# PhotoBoothRaspPi.net
KiCad netlist of a schematic drawn in EAGLE
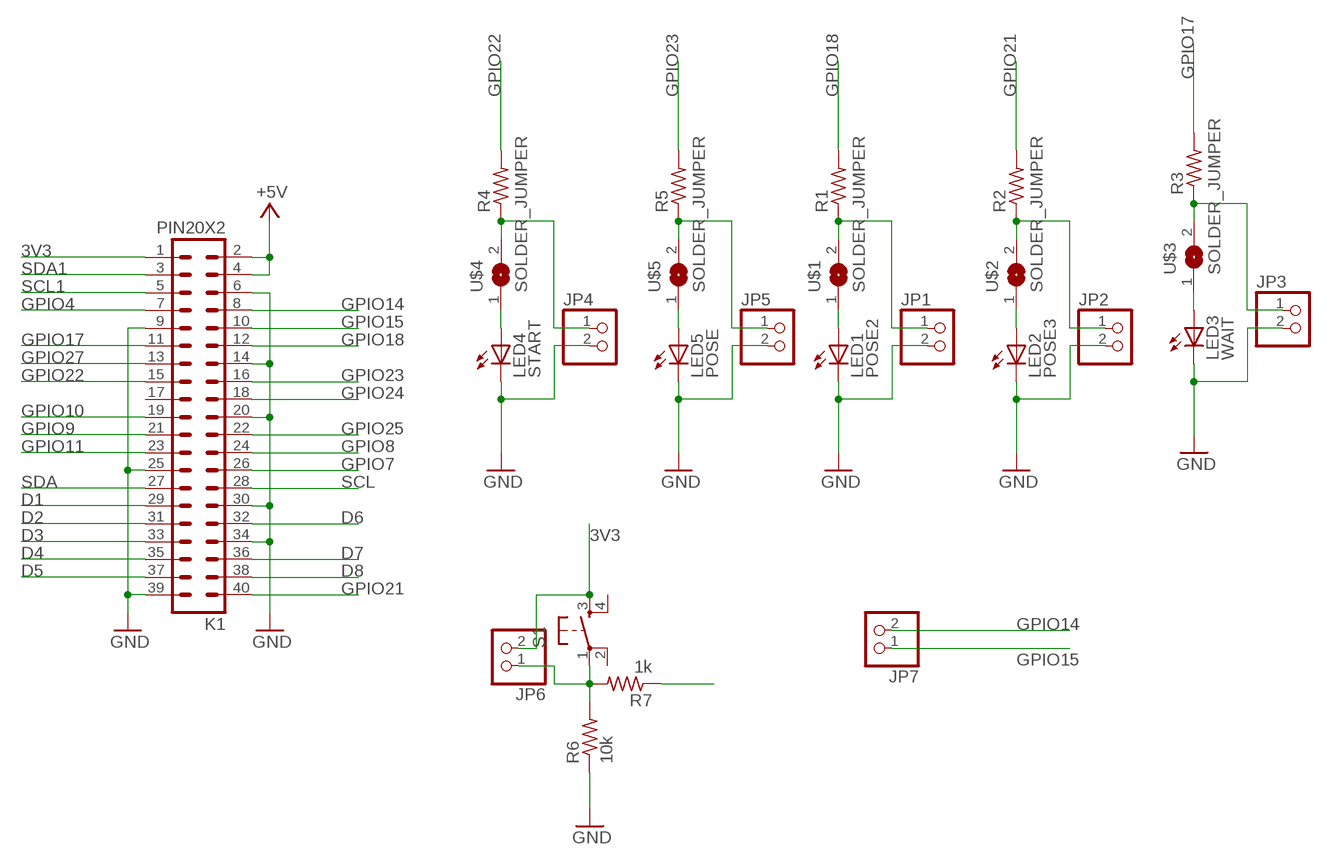
[diagram p0: schematic, sheet 1]

(export (version "E")
  (design (tool "Eeschema 10.0.6"))
  (components
    (comp (ref "JP1")
      (value "PINHD-1X2")
      (footprint "eagle-import:1X02")
      (libsource (lib "eagle-import") (part "PINHD-1X2"))
    )
    (comp (ref "JP2")
      (value "PINHD-1X2")
      (footprint "eagle-import:1X02")
      (libsource (lib "eagle-import") (part "PINHD-1X2"))
    )
    (comp (ref "JP3")
      (value "PINHD-1X2")
      (footprint "eagle-import:1X02")
      (libsource (lib "eagle-import") (part "PINHD-1X2"))
    )
    (comp (ref "JP4")
      (value "PINHD-1X2")
      (footprint "eagle-import:1X02")
      (libsource (lib "eagle-import") (part "PINHD-1X2"))
    )
    (comp (ref "JP5")
      (value "PINHD-1X2")
      (footprint "eagle-import:1X02")
      (libsource (lib "eagle-import") (part "PINHD-1X2"))
    )
    (comp (ref "JP6")
      (value "PINHD-1X2")
      (footprint "eagle-import:1X02")
      (libsource (lib "eagle-import") (part "PINHD-1X2"))
    )
    (comp (ref "JP7")
      (value "PINHD-1X2")
      (footprint "eagle-import:1X02")
      (libsource (lib "eagle-import") (part "PINHD-1X2"))
    )
    (comp (ref "K1")
      (value "PIN20X2")
      (footprint "eagle-import:PIN_20X2")
      (libsource (lib "eagle-import") (part "PIN20X2"))
    )
    (comp (ref "LED1")
      (value "POSE2")
      (footprint "eagle-import:CHIPLED_1206")
      (libsource (lib "eagle-import") (part "LEDCHIPLED_1206"))
    )
    (comp (ref "LED2")
      (value "POSE3")
      (footprint "eagle-import:CHIPLED_1206")
      (libsource (lib "eagle-import") (part "LEDCHIPLED_1206"))
    )
    (comp (ref "LED3")
      (value "WAIT")
      (footprint "eagle-import:CHIPLED_1206")
      (libsource (lib "eagle-import") (part "LEDCHIPLED_1206"))
    )
    (comp (ref "LED4")
      (value "START")
      (footprint "eagle-import:CHIPLED_1206")
      (libsource (lib "eagle-import") (part "LEDCHIPLED_1206"))
    )
    (comp (ref "LED5")
      (value "POSE")
      (footprint "eagle-import:CHIPLED_1206")
      (libsource (lib "eagle-import") (part "LEDCHIPLED_1206"))
    )
    (comp (ref "R1")
      (value "RES-US1206FAB")
      (footprint "eagle-import:R1206FAB")
      (libsource (lib "eagle-import") (part "RES-US1206FAB"))
    )
    (comp (ref "R2")
      (value "RES-US1206FAB")
      (footprint "eagle-import:R1206FAB")
      (libsource (lib "eagle-import") (part "RES-US1206FAB"))
    )
    (comp (ref "R3")
      (value "RES-US1206FAB")
      (footprint "eagle-import:R1206FAB")
      (libsource (lib "eagle-import") (part "RES-US1206FAB"))
    )
    (comp (ref "R4")
      (value "RES-US1206FAB")
      (footprint "eagle-import:R1206FAB")
      (libsource (lib "eagle-import") (part "RES-US1206FAB"))
    )
    (comp (ref "R5")
      (value "RES-US1206FAB")
      (footprint "eagle-import:R1206FAB")
      (libsource (lib "eagle-import") (part "RES-US1206FAB"))
    )
    (comp (ref "R6")
      (value "10k")
      (footprint "eagle-import:R1206FAB")
      (libsource (lib "eagle-import") (part "RES-US1206FAB"))
    )
    (comp (ref "R7")
      (value "1k")
      (footprint "eagle-import:R1206FAB")
      (libsource (lib "eagle-import") (part "RES-US1206FAB"))
    )
    (comp (ref "S1")
      (value "6MM_SWITCH6MM_SWITCH")
      (footprint "eagle-import:6MM_SWITCH")
      (libsource (lib "eagle-import") (part "6MM_SWITCH6MM_SWITCH"))
    )
    (comp (ref "U$1")
      (value "SOLDER_JUMPER")
      (footprint "eagle-import:SJFAB")
      (libsource (lib "eagle-import") (part "SOLDER_JUMPER"))
    )
    (comp (ref "U$2")
      (value "SOLDER_JUMPER")
      (footprint "eagle-import:SJFAB")
      (libsource (lib "eagle-import") (part "SOLDER_JUMPER"))
    )
    (comp (ref "U$3")
      (value "SOLDER_JUMPER")
      (footprint "eagle-import:SJFAB")
      (libsource (lib "eagle-import") (part "SOLDER_JUMPER"))
    )
    (comp (ref "U$4")
      (value "SOLDER_JUMPER")
      (footprint "eagle-import:SJFAB")
      (libsource (lib "eagle-import") (part "SOLDER_JUMPER"))
    )
    (comp (ref "U$5")
      (value "SOLDER_JUMPER")
      (footprint "eagle-import:SJFAB")
      (libsource (lib "eagle-import") (part "SOLDER_JUMPER"))
    )
  )
  (nets
    (net (code "1") (name "+5V") (class "Default")
      (node (ref "K1") (pin "2") (pinfunction "2_2") (pintype "passive"))
      (node (ref "K1") (pin "4") (pinfunction "4_4") (pintype "passive"))
    )
    (net (code "2") (name "/3V3") (class "Default")
      (node (ref "JP6") (pin "2") (pinfunction "2_2") (pintype "passive"))
      (node (ref "K1") (pin "1") (pinfunction "1_1") (pintype "passive"))
      (node (ref "S1") (pin "3") (pinfunction "S_3") (pintype "passive"))
    )
    (net (code "3") (name "/D1") (class "Default")
      (node (ref "K1") (pin "29") (pinfunction "29_29") (pintype "passive"))
    )
    (net (code "4") (name "/D2") (class "Default")
      (node (ref "K1") (pin "31") (pinfunction "31_31") (pintype "passive"))
    )
    (net (code "5") (name "/D3") (class "Default")
      (node (ref "K1") (pin "33") (pinfunction "33_33") (pintype "passive"))
    )
    (net (code "6") (name "/D4") (class "Default")
      (node (ref "K1") (pin "35") (pinfunction "35_35") (pintype "passive"))
    )
    (net (code "7") (name "/D5") (class "Default")
      (node (ref "K1") (pin "37") (pinfunction "37_37") (pintype "passive"))
    )
    (net (code "8") (name "/D6") (class "Default")
      (node (ref "K1") (pin "32") (pinfunction "32_32") (pintype "passive"))
    )
    (net (code "9") (name "/D7") (class "Default")
      (node (ref "K1") (pin "36") (pinfunction "36_36") (pintype "passive"))
    )
    (net (code "10") (name "/D8") (class "Default")
      (node (ref "K1") (pin "38") (pinfunction "38_38") (pintype "passive"))
    )
    (net (code "11") (name "/GPIO4") (class "Default")
      (node (ref "K1") (pin "7") (pinfunction "7_7") (pintype "passive"))
    )
    (net (code "12") (name "/GPIO7") (class "Default")
      (node (ref "K1") (pin "26") (pinfunction "26_26") (pintype "passive"))
    )
    (net (code "13") (name "/GPIO8") (class "Default")
      (node (ref "K1") (pin "24") (pinfunction "24_24") (pintype "passive"))
    )
    (net (code "14") (name "/GPIO9") (class "Default")
      (node (ref "K1") (pin "21") (pinfunction "21_21") (pintype "passive"))
    )
    (net (code "15") (name "/GPIO10") (class "Default")
      (node (ref "K1") (pin "19") (pinfunction "19_19") (pintype "passive"))
    )
    (net (code "16") (name "/GPIO11") (class "Default")
      (node (ref "K1") (pin "23") (pinfunction "23_23") (pintype "passive"))
    )
    (net (code "17") (name "/GPIO14") (class "Default")
      (node (ref "JP7") (pin "2") (pinfunction "2_2") (pintype "passive"))
      (node (ref "K1") (pin "8") (pinfunction "8_8") (pintype "passive"))
    )
    (net (code "18") (name "/GPIO15") (class "Default")
      (node (ref "JP7") (pin "1") (pinfunction "1_1") (pintype "passive"))
      (node (ref "K1") (pin "10") (pinfunction "10_10") (pintype "passive"))
    )
    (net (code "19") (name "/GPIO17") (class "Default")
      (node (ref "K1") (pin "11") (pinfunction "11_11") (pintype "passive"))
      (node (ref "R3") (pin "2") (pinfunction "2_2") (pintype "passive"))
    )
    (net (code "20") (name "/GPIO18") (class "Default")
      (node (ref "K1") (pin "12") (pinfunction "12_12") (pintype "passive"))
      (node (ref "R1") (pin "2") (pinfunction "2_2") (pintype "passive"))
    )
    (net (code "21") (name "/GPIO21") (class "Default")
      (node (ref "K1") (pin "40") (pinfunction "40_40") (pintype "passive"))
      (node (ref "R2") (pin "2") (pinfunction "2_2") (pintype "passive"))
    )
    (net (code "22") (name "/GPIO22") (class "Default")
      (node (ref "K1") (pin "15") (pinfunction "15_15") (pintype "passive"))
      (node (ref "R4") (pin "2") (pinfunction "2_2") (pintype "passive"))
    )
    (net (code "23") (name "/GPIO23") (class "Default")
      (node (ref "K1") (pin "16") (pinfunction "16_16") (pintype "passive"))
      (node (ref "R5") (pin "2") (pinfunction "2_2") (pintype "passive"))
    )
    (net (code "24") (name "/GPIO24") (class "Default")
      (node (ref "K1") (pin "18") (pinfunction "18_18") (pintype "passive"))
      (node (ref "R7") (pin "1") (pinfunction "1_1") (pintype "passive"))
    )
    (net (code "25") (name "/GPIO25") (class "Default")
      (node (ref "K1") (pin "22") (pinfunction "22_22") (pintype "passive"))
    )
    (net (code "26") (name "/GPIO27") (class "Default")
      (node (ref "K1") (pin "13") (pinfunction "13_13") (pintype "passive"))
    )
    (net (code "27") (name "/SCL") (class "Default")
      (node (ref "K1") (pin "28") (pinfunction "28_28") (pintype "passive"))
    )
    (net (code "28") (name "/SCL1") (class "Default")
      (node (ref "K1") (pin "5") (pinfunction "5_5") (pintype "passive"))
    )
    (net (code "29") (name "/SDA") (class "Default")
      (node (ref "K1") (pin "27") (pinfunction "27_27") (pintype "passive"))
    )
    (net (code "30") (name "/SDA1") (class "Default")
      (node (ref "K1") (pin "3") (pinfunction "3_3") (pintype "passive"))
    )
    (net (code "31") (name "GND") (class "Default")
      (node (ref "JP1") (pin "2") (pinfunction "2_2") (pintype "passive"))
      (node (ref "JP2") (pin "2") (pinfunction "2_2") (pintype "passive"))
      (node (ref "JP3") (pin "2") (pinfunction "2_2") (pintype "passive"))
      (node (ref "JP4") (pin "2") (pinfunction "2_2") (pintype "passive"))
      (node (ref "JP5") (pin "2") (pinfunction "2_2") (pintype "passive"))
      (node (ref "K1") (pin "14") (pinfunction "14_14") (pintype "passive"))
      (node (ref "K1") (pin "20") (pinfunction "20_20") (pintype "passive"))
      (node (ref "K1") (pin "25") (pinfunction "25_25") (pintype "passive"))
      (node (ref "K1") (pin "30") (pinfunction "30_30") (pintype "passive"))
      (node (ref "K1") (pin "34") (pinfunction "34_34") (pintype "passive"))
      (node (ref "K1") (pin "39") (pinfunction "39_39") (pintype "passive"))
      (node (ref "K1") (pin "6") (pinfunction "6_6") (pintype "passive"))
      (node (ref "K1") (pin "9") (pinfunction "9_9") (pintype "passive"))
      (node (ref "LED1") (pin "C") (pinfunction "C_C") (pintype "passive"))
      (node (ref "LED2") (pin "C") (pinfunction "C_C") (pintype "passive"))
      (node (ref "LED3") (pin "C") (pinfunction "C_C") (pintype "passive"))
      (node (ref "LED4") (pin "C") (pinfunction "C_C") (pintype "passive"))
      (node (ref "LED5") (pin "C") (pinfunction "C_C") (pintype "passive"))
      (node (ref "R6") (pin "1") (pinfunction "1_1") (pintype "passive"))
    )
    (net (code "32") (name "Net-(JP1-Pad1)") (class "Default")
      (node (ref "JP1") (pin "1") (pinfunction "1_1") (pintype "passive"))
      (node (ref "R1") (pin "1") (pinfunction "1_1") (pintype "passive"))
      (node (ref "U$1") (pin "2") (pinfunction "2_2") (pintype "passive"))
    )
    (net (code "33") (name "Net-(JP2-Pad1)") (class "Default")
      (node (ref "JP2") (pin "1") (pinfunction "1_1") (pintype "passive"))
      (node (ref "R2") (pin "1") (pinfunction "1_1") (pintype "passive"))
      (node (ref "U$2") (pin "2") (pinfunction "2_2") (pintype "passive"))
    )
    (net (code "34") (name "Net-(JP3-Pad1)") (class "Default")
      (node (ref "JP3") (pin "1") (pinfunction "1_1") (pintype "passive"))
      (node (ref "R3") (pin "1") (pinfunction "1_1") (pintype "passive"))
      (node (ref "U$3") (pin "2") (pinfunction "2_2") (pintype "passive"))
    )
    (net (code "35") (name "Net-(JP4-Pad1)") (class "Default")
      (node (ref "JP4") (pin "1") (pinfunction "1_1") (pintype "passive"))
      (node (ref "R4") (pin "1") (pinfunction "1_1") (pintype "passive"))
      (node (ref "U$4") (pin "2") (pinfunction "2_2") (pintype "passive"))
    )
    (net (code "36") (name "Net-(JP5-Pad1)") (class "Default")
      (node (ref "JP5") (pin "1") (pinfunction "1_1") (pintype "passive"))
      (node (ref "R5") (pin "1") (pinfunction "1_1") (pintype "passive"))
      (node (ref "U$5") (pin "2") (pinfunction "2_2") (pintype "passive"))
    )
    (net (code "37") (name "Net-(LED1-PadA)") (class "Default")
      (node (ref "LED1") (pin "A") (pinfunction "A_A") (pintype "passive"))
      (node (ref "U$1") (pin "1") (pinfunction "1_1") (pintype "passive"))
    )
    (net (code "38") (name "Net-(LED2-PadA)") (class "Default")
      (node (ref "LED2") (pin "A") (pinfunction "A_A") (pintype "passive"))
      (node (ref "U$2") (pin "1") (pinfunction "1_1") (pintype "passive"))
    )
    (net (code "39") (name "Net-(LED3-PadA)") (class "Default")
      (node (ref "LED3") (pin "A") (pinfunction "A_A") (pintype "passive"))
      (node (ref "U$3") (pin "1") (pinfunction "1_1") (pintype "passive"))
    )
    (net (code "40") (name "Net-(LED4-PadA)") (class "Default")
      (node (ref "LED4") (pin "A") (pinfunction "A_A") (pintype "passive"))
      (node (ref "U$4") (pin "1") (pinfunction "1_1") (pintype "passive"))
    )
    (net (code "41") (name "Net-(LED5-PadA)") (class "Default")
      (node (ref "LED5") (pin "A") (pinfunction "A_A") (pintype "passive"))
      (node (ref "U$5") (pin "1") (pinfunction "1_1") (pintype "passive"))
    )
    (net (code "42") (name "Net-(S1-P)") (class "Default")
      (node (ref "JP6") (pin "1") (pinfunction "1_1") (pintype "passive"))
      (node (ref "R6") (pin "2") (pinfunction "2_2") (pintype "passive"))
      (node (ref "R7") (pin "2") (pinfunction "2_2") (pintype "passive"))
      (node (ref "S1") (pin "1") (pinfunction "P_1") (pintype "passive"))
    )
    (net (code "43") (name "unconnected-(K1-Pad17)") (class "Default")
      (node (ref "K1") (pin "17") (pinfunction "17_17") (pintype "passive"))
    )
    (net (code "44") (name "unconnected-(S1-P1-Pad2)") (class "Default")
      (node (ref "S1") (pin "2") (pinfunction "P1_2") (pintype "passive"))
    )
    (net (code "45") (name "unconnected-(S1-S1-Pad4)") (class "Default")
      (node (ref "S1") (pin "4") (pinfunction "S1_4") (pintype "passive"))
    )
  )
)
